# cv02hartan.net
KiCad netlist of a schematic drawn in EAGLE
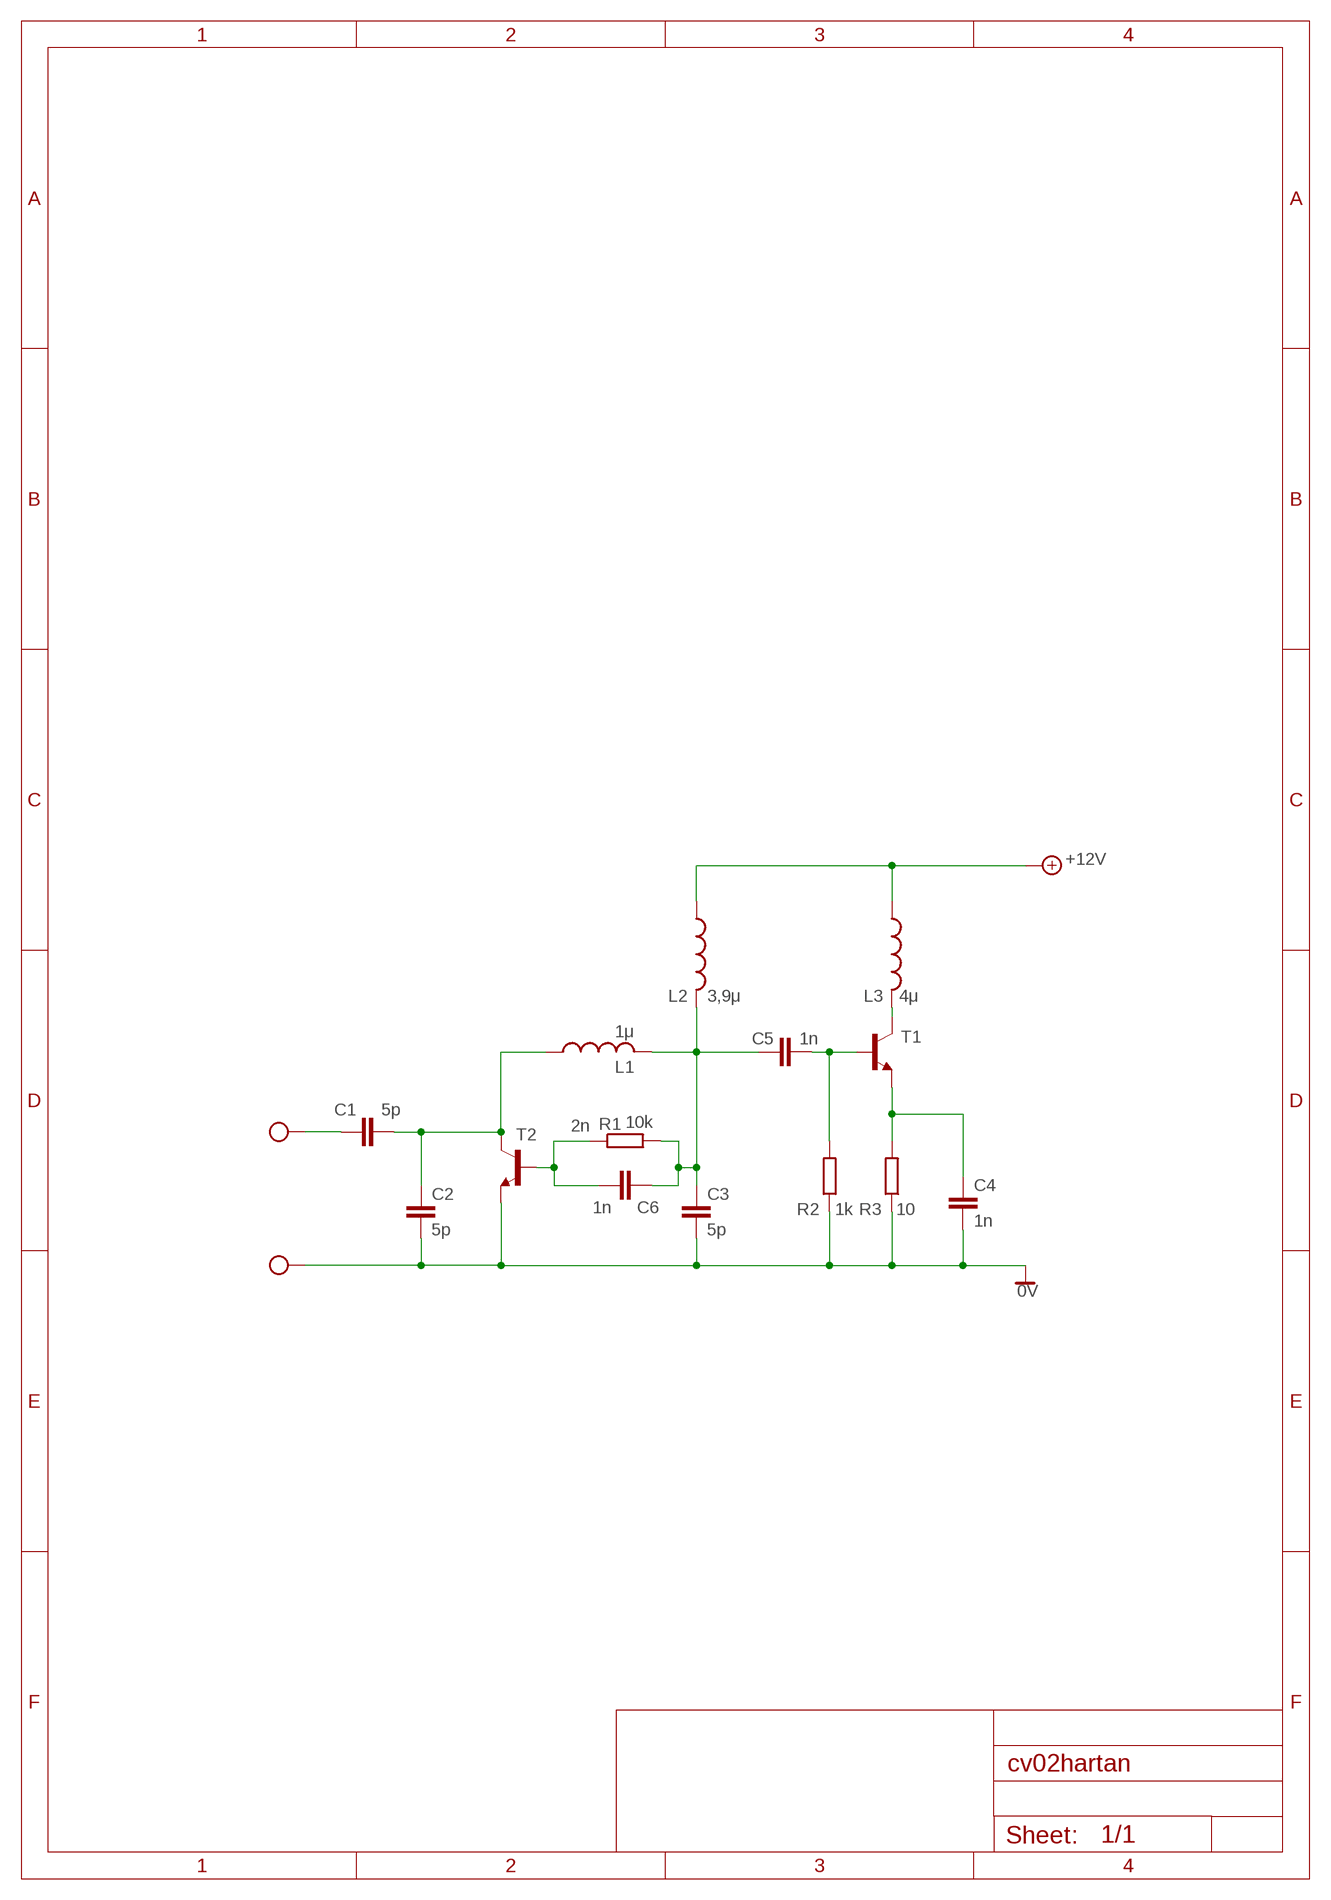
[diagram p0: schematic, sheet 1]

(export (version "E")
  (design (tool "Eeschema 10.0.6"))
  (components
    (comp (ref "C1")
      (value "5p")
      (footprint "eagle-import:C2.5-3")
      (libsource (lib "eagle-import") (part "C2,5-3"))
    )
    (comp (ref "C2")
      (value "5p")
      (footprint "eagle-import:C2.5-3")
      (libsource (lib "eagle-import") (part "C2,5-3"))
    )
    (comp (ref "C3")
      (value "5p")
      (footprint "eagle-import:C2.5-3")
      (libsource (lib "eagle-import") (part "C2,5-3"))
    )
    (comp (ref "C4")
      (value "1n")
      (footprint "eagle-import:C2.5-3")
      (libsource (lib "eagle-import") (part "C2,5-3"))
    )
    (comp (ref "C5")
      (value "1n")
      (footprint "eagle-import:C2.5-3")
      (libsource (lib "eagle-import") (part "C2,5-3"))
    )
    (comp (ref "C6")
      (value "1n")
      (footprint "eagle-import:C025-024X044")
      (libsource (lib "eagle-import") (part "C-EU025-024X044"))
    )
    (comp (ref "L1")
      (value "1μ")
      (footprint "eagle-import:0204_5")
      (libsource (lib "eagle-import") (part "L-US0204/5"))
    )
    (comp (ref "L2")
      (value "3,9μ")
      (footprint "eagle-import:0204_5")
      (libsource (lib "eagle-import") (part "L-US0204/5"))
    )
    (comp (ref "L3")
      (value "4μ")
      (footprint "eagle-import:0204_5")
      (libsource (lib "eagle-import") (part "L-US0204/5"))
    )
    (comp (ref "R1")
      (value "10k")
      (footprint "eagle-import:0204V")
      (libsource (lib "eagle-import") (part "R-EU_0204/2V"))
    )
    (comp (ref "R2")
      (value "1k")
      (footprint "eagle-import:0204V")
      (libsource (lib "eagle-import") (part "R-EU_0204/2V"))
    )
    (comp (ref "R3")
      (value "10")
      (footprint "eagle-import:0204V")
      (libsource (lib "eagle-import") (part "R-EU_0204/2V"))
    )
    (comp (ref "T1")
      (value "2N2222A-NPN-TO18-EBC")
      (footprint "eagle-import:TO18")
      (libsource (lib "eagle-import") (part "-NPN-TO18-EBC2N2222A"))
    )
    (comp (ref "T2")
      (value "2n")
      (footprint "eagle-import:TO18")
      (libsource (lib "eagle-import") (part "-NPN-TO18-EBC2N2222A"))
    )
  )
  (nets
    (net (code "1") (name "+12V") (class "Default")
      (node (ref "L2") (pin "1") (pinfunction "1_1") (pintype "passive"))
      (node (ref "L3") (pin "1") (pinfunction "1_1") (pintype "passive"))
    )
    (net (code "2") (name "0V") (class "Default")
      (node (ref "C1") (pin "1") (pinfunction "1_1") (pintype "passive"))
      (node (ref "C2") (pin "2") (pinfunction "2_2") (pintype "passive"))
      (node (ref "C3") (pin "2") (pinfunction "2_2") (pintype "passive"))
      (node (ref "C4") (pin "2") (pinfunction "2_2") (pintype "passive"))
      (node (ref "R2") (pin "1") (pinfunction "1_1") (pintype "passive"))
      (node (ref "R3") (pin "1") (pinfunction "1_1") (pintype "passive"))
      (node (ref "T2") (pin "1") (pinfunction "E_1") (pintype "passive"))
    )
    (net (code "3") (name "Net-(C3-Pad1)") (class "Default")
      (node (ref "C3") (pin "1") (pinfunction "1_1") (pintype "passive"))
      (node (ref "C5") (pin "1") (pinfunction "1_1") (pintype "passive"))
      (node (ref "C6") (pin "1") (pinfunction "1_1") (pintype "passive"))
      (node (ref "L1") (pin "2") (pinfunction "2_2") (pintype "passive"))
      (node (ref "L2") (pin "2") (pinfunction "2_2") (pintype "passive"))
      (node (ref "R1") (pin "2") (pinfunction "2_2") (pintype "passive"))
    )
    (net (code "4") (name "Net-(T1-B)") (class "Default")
      (node (ref "C5") (pin "2") (pinfunction "2_2") (pintype "passive"))
      (node (ref "R2") (pin "2") (pinfunction "2_2") (pintype "passive"))
      (node (ref "T1") (pin "2") (pinfunction "B_2") (pintype "passive"))
    )
    (net (code "5") (name "Net-(T1-C)") (class "Default")
      (node (ref "L3") (pin "2") (pinfunction "2_2") (pintype "passive"))
      (node (ref "T1") (pin "3") (pinfunction "C_3") (pintype "passive"))
    )
    (net (code "6") (name "Net-(T1-E)") (class "Default")
      (node (ref "C4") (pin "1") (pinfunction "1_1") (pintype "passive"))
      (node (ref "R3") (pin "2") (pinfunction "2_2") (pintype "passive"))
      (node (ref "T1") (pin "1") (pinfunction "E_1") (pintype "passive"))
    )
    (net (code "7") (name "Net-(T2-B)") (class "Default")
      (node (ref "C6") (pin "2") (pinfunction "2_2") (pintype "passive"))
      (node (ref "R1") (pin "1") (pinfunction "1_1") (pintype "passive"))
      (node (ref "T2") (pin "2") (pinfunction "B_2") (pintype "passive"))
    )
    (net (code "8") (name "Net-(T2-C)") (class "Default")
      (node (ref "C1") (pin "2") (pinfunction "2_2") (pintype "passive"))
      (node (ref "C2") (pin "1") (pinfunction "1_1") (pintype "passive"))
      (node (ref "L1") (pin "1") (pinfunction "1_1") (pintype "passive"))
      (node (ref "T2") (pin "3") (pinfunction "C_3") (pintype "passive"))
    )
  )
)
